# ModemExt2.net
KiCad netlist of a schematic drawn in Altium Designer
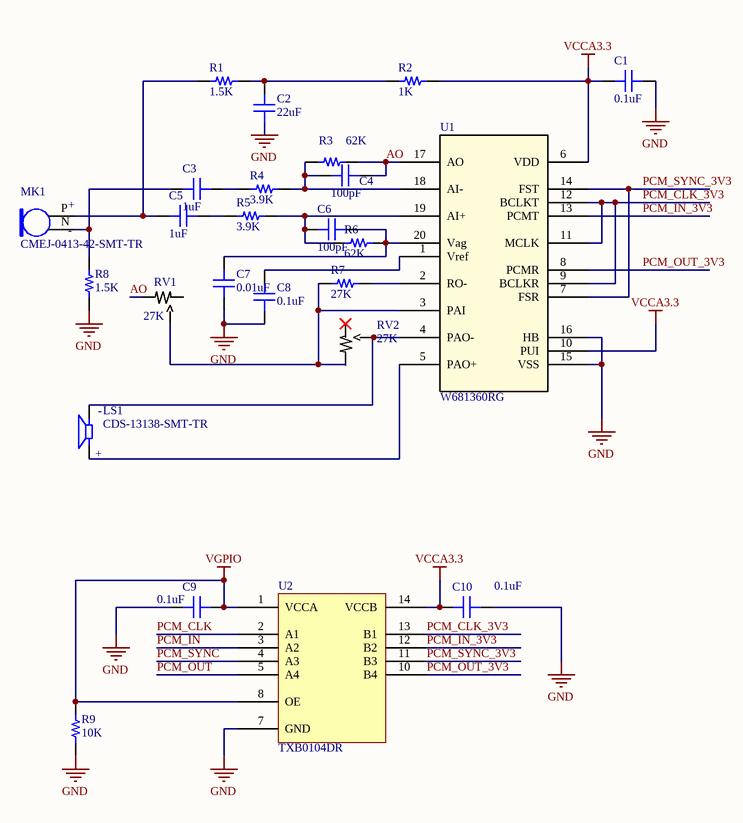
[diagram p0: ModemExt2.SchDoc]

(export (version "E")
  (design (tool "Eeschema 10.0.6"))
  (components
    (comp (ref "C1")
      (value "0.1uF")
      (footprint "CAP 0402_1005")
      (description "CAP CER 2.2UF 10V X5R 0402\r\ngrm155r61a")
      (fields
        (field (name "PART NUMBER") "GRM155R61A225ME95D")
        (field (name "MANUFACTURER") "Murata Electronics")
      )
      (libsource (lib "Celestial Altium Library - altium_library") (part "Capacitor"))
    )
    (comp (ref "C2")
      (value "22uF")
      (footprint "CAP 0402_1005")
      (description "CAP CER 2.2UF 10V X5R 0402\r\ngrm155r61a")
      (fields
        (field (name "PART NUMBER") "GRM155R61A225ME95D")
        (field (name "MANUFACTURER") "Murata Electronics")
      )
      (libsource (lib "Celestial Altium Library - altium_library") (part "Capacitor"))
    )
    (comp (ref "C3")
      (value "1uF")
      (footprint "CAP 0402_1005")
      (description "CAP CER 2.2UF 10V X5R 0402\r\ngrm155r61a")
      (fields
        (field (name "PART NUMBER") "GRM155R61A225ME95D")
        (field (name "MANUFACTURER") "Murata Electronics")
      )
      (libsource (lib "Celestial Altium Library - altium_library") (part "Capacitor"))
    )
    (comp (ref "C4")
      (value "100pF")
      (footprint "CAP 0402_1005")
      (description "CAP CER 2.2UF 10V X5R 0402\r\ngrm155r61a")
      (fields
        (field (name "PART NUMBER") "GRM155R61A225ME95D")
        (field (name "MANUFACTURER") "Murata Electronics")
      )
      (libsource (lib "Celestial Altium Library - altium_library") (part "Capacitor"))
    )
    (comp (ref "C5")
      (value "1uF")
      (footprint "CAP 0402_1005")
      (description "CAP CER 2.2UF 10V X5R 0402\r\ngrm155r61a")
      (fields
        (field (name "PART NUMBER") "GRM155R61A225ME95D")
        (field (name "MANUFACTURER") "Murata Electronics")
      )
      (libsource (lib "Celestial Altium Library - altium_library") (part "Capacitor"))
    )
    (comp (ref "C6")
      (value "100pF")
      (footprint "CAP 0402_1005")
      (description "CAP CER 2.2UF 10V X5R 0402\r\ngrm155r61a")
      (fields
        (field (name "PART NUMBER") "GRM155R61A225ME95D")
        (field (name "MANUFACTURER") "Murata Electronics")
      )
      (libsource (lib "Celestial Altium Library - altium_library") (part "Capacitor"))
    )
    (comp (ref "C7")
      (value "0.01uF")
      (footprint "CAP 0402_1005")
      (description "CAP CER 2.2UF 10V X5R 0402\r\ngrm155r61a")
      (fields
        (field (name "PART NUMBER") "GRM155R61A225ME95D")
        (field (name "MANUFACTURER") "Murata Electronics")
      )
      (libsource (lib "Celestial Altium Library - altium_library") (part "Capacitor"))
    )
    (comp (ref "C8")
      (value "0.1uF")
      (footprint "CAP 0402_1005")
      (description "CAP CER 2.2UF 10V X5R 0402\r\ngrm155r61a")
      (fields
        (field (name "PART NUMBER") "GRM155R61A225ME95D")
        (field (name "MANUFACTURER") "Murata Electronics")
      )
      (libsource (lib "Celestial Altium Library - altium_library") (part "Capacitor"))
    )
    (comp (ref "C9")
      (value "0.1uF")
      (footprint "CAP 0402_1005")
      (description "CAP CER 2.2UF 10V X5R 0402\r\ngrm155r61a")
      (fields
        (field (name "PART NUMBER") "GRM155R61A225ME95D")
        (field (name "MANUFACTURER") "Murata Electronics")
      )
      (libsource (lib "Celestial Altium Library - altium_library") (part "Capacitor"))
    )
    (comp (ref "C10")
      (value "0.1uF")
      (footprint "CAP 0402_1005")
      (description "CAP CER 2.2UF 10V X5R 0402\r\ngrm155r61a")
      (fields
        (field (name "PART NUMBER") "GRM155R61A225ME95D")
        (field (name "MANUFACTURER") "Murata Electronics")
      )
      (libsource (lib "Celestial Altium Library - altium_library") (part "Capacitor"))
    )
    (comp (ref "LS1")
      (value "CDS-13138-SMT-TR")
      (footprint "SPKR_CDS-13138-SMT-TR")
      (description "13 mm, Square Frame, 0.7 W, 8 Ohm, Samarium Cobalt Magnet, Mylar Cone")
      (fields (field (name "MF") "CUI Devices"))
      (libsource (lib "Schlib1") (part "CDS-13138-SMT-TR"))
    )
    (comp (ref "MK1")
      (value "CMEJ-0413-42-SMT-TR")
      (footprint "MIC_CMEJ-0413-42-SMT-TR")
      (description "4.0 mm, Omnidirectional, Surface Mount, 2 Vdc, Electret Condenser Microphone")
      (fields (field (name "MF") "CUI Devices"))
      (libsource (lib "Schlib1") (part "CMEJ-0413-42-SMT-TR"))
    )
    (comp (ref "R1")
      (value "1.5K")
      (footprint "RES 0603_1608")
      (description "RES SMD 10K OHM 1% 1/10W 0603")
      (fields (field (name "PART NUMBER") "AC0603FR-0710KL") (field (name "MANUFACTURER") "Yageo"))
      (libsource (lib "Celestial Altium Library - altium_library") (part "Resistor"))
    )
    (comp (ref "R2")
      (value "1K")
      (footprint "RES 0603_1608")
      (description "RES SMD 10K OHM 1% 1/10W 0603")
      (fields (field (name "PART NUMBER") "AC0603FR-0710KL") (field (name "MANUFACTURER") "Yageo"))
      (libsource (lib "Celestial Altium Library - altium_library") (part "Resistor"))
    )
    (comp (ref "R3")
      (value "62K")
      (footprint "RES 0603_1608")
      (description "RES SMD 10K OHM 1% 1/10W 0603")
      (fields (field (name "PART NUMBER") "AC0603FR-0710KL") (field (name "MANUFACTURER") "Yageo"))
      (libsource (lib "Celestial Altium Library - altium_library") (part "Resistor"))
    )
    (comp (ref "R4")
      (value "3.9K")
      (footprint "RES 0603_1608")
      (description "RES SMD 10K OHM 1% 1/10W 0603")
      (fields (field (name "PART NUMBER") "AC0603FR-0710KL") (field (name "MANUFACTURER") "Yageo"))
      (libsource (lib "Celestial Altium Library - altium_library") (part "Resistor"))
    )
    (comp (ref "R5")
      (value "3.9K")
      (footprint "RES 0603_1608")
      (description "RES SMD 10K OHM 1% 1/10W 0603")
      (fields (field (name "PART NUMBER") "AC0603FR-0710KL") (field (name "MANUFACTURER") "Yageo"))
      (libsource (lib "Celestial Altium Library - altium_library") (part "Resistor"))
    )
    (comp (ref "R6")
      (value "62K")
      (footprint "RES 0603_1608")
      (description "RES SMD 10K OHM 1% 1/10W 0603")
      (fields (field (name "PART NUMBER") "AC0603FR-0710KL") (field (name "MANUFACTURER") "Yageo"))
      (libsource (lib "Celestial Altium Library - altium_library") (part "Resistor"))
    )
    (comp (ref "R7")
      (value "27K")
      (footprint "RES 0603_1608")
      (description "RES SMD 10K OHM 1% 1/10W 0603")
      (fields (field (name "PART NUMBER") "AC0603FR-0710KL") (field (name "MANUFACTURER") "Yageo"))
      (libsource (lib "Celestial Altium Library - altium_library") (part "Resistor"))
    )
    (comp (ref "R8")
      (value "1.5K")
      (footprint "RES 0603_1608")
      (description "RES SMD 10K OHM 1% 1/10W 0603")
      (fields (field (name "PART NUMBER") "AC0603FR-0710KL") (field (name "MANUFACTURER") "Yageo"))
      (libsource (lib "Celestial Altium Library - altium_library") (part "Resistor"))
    )
    (comp (ref "R9")
      (value "10K")
      (footprint "RES 0603_1608")
      (description "RES SMD 10K OHM 1% 1/10W 0603")
      (fields (field (name "PART NUMBER") "AC0603FR-0710KL") (field (name "MANUFACTURER") "Yageo"))
      (libsource (lib "Celestial Altium Library - altium_library") (part "Resistor"))
    )
    (comp (ref "RV1")
      (value "27K")
      (footprint "*TRIM_3313J-1-503E")
      (fields (field (name "Comment") "3313J-1-503E"))
      (libsource (lib "Schlib1") (part "3313J-1-503E"))
    )
    (comp (ref "RV2")
      (value "27K")
      (footprint "*TRIM_3313J-1-503E")
      (fields (field (name "Comment") "3313J-1-503E"))
      (libsource (lib "Schlib1") (part "3313J-1-503E"))
    )
    (comp (ref "U1")
      (value "W681360RG")
      (footprint "SSOP20_MC_MCH")
      (description "No Description Available")
      (fields
        (field (name "MANUFACTURER_PART_NUMBER") "PIC16F685-E/SS")
        (field (name "COPYRIGHT") "Copyright (C) 2018 Accelerated Designs. All rights reserved")
      )
      (libsource (lib "Schlib1") (part "Audio Codec"))
    )
    (comp (ref "U2")
      (value "TXB0104DR")
      (footprint "TI SOIC-14 D")
      (description "IC TRNSLTR BIDIRECTIONAL 14SOIC")
      (fields (field (name "MANUFACTURER") "Texas Instruments"))
      (libsource (lib "Celestial Altium Library - altium_library") (part "TI TXB0104"))
    )
  )
  (nets
    (net (code "1") (name "/AO") (class "Default")
      (node (ref "C4") (pin "1") (pinfunction "1_1") (pintype "passive"))
      (node (ref "R3") (pin "1") (pinfunction "1_1") (pintype "passive"))
      (node (ref "RV1") (pin "1") (pinfunction "CCW_1") (pintype "passive"))
      (node (ref "U1") (pin "17") (pinfunction "AO_17") (pintype "passive"))
    )
    (net (code "2") (name "/PCM_CLK") (class "Default")
      (node (ref "U2") (pin "2") (pinfunction "A1_2") (pintype "passive"))
    )
    (net (code "3") (name "/PCM_CLK_3V3") (class "Default")
      (node (ref "U1") (pin "11") (pinfunction "MCLK_11") (pintype "passive"))
      (node (ref "U1") (pin "12") (pinfunction "BCLKT_12") (pintype "passive"))
      (node (ref "U1") (pin "9") (pinfunction "BCLKR_9") (pintype "passive"))
      (node (ref "U2") (pin "13") (pinfunction "B1_13") (pintype "passive"))
    )
    (net (code "4") (name "/PCM_IN") (class "Default")
      (node (ref "U2") (pin "3") (pinfunction "A2_3") (pintype "passive"))
    )
    (net (code "5") (name "/PCM_IN_3V3") (class "Default")
      (node (ref "U1") (pin "13") (pinfunction "PCMT_13") (pintype "passive"))
      (node (ref "U2") (pin "12") (pinfunction "B2_12") (pintype "passive"))
    )
    (net (code "6") (name "/PCM_OUT") (class "Default")
      (node (ref "U2") (pin "5") (pinfunction "A4_5") (pintype "passive"))
    )
    (net (code "7") (name "/PCM_OUT_3V3") (class "Default")
      (node (ref "U1") (pin "8") (pinfunction "PCMR_8") (pintype "passive"))
      (node (ref "U2") (pin "10") (pinfunction "B4_10") (pintype "passive"))
    )
    (net (code "8") (name "/PCM_SYNC") (class "Default")
      (node (ref "U2") (pin "4") (pinfunction "A3_4") (pintype "passive"))
    )
    (net (code "9") (name "/PCM_SYNC_3V3") (class "Default")
      (node (ref "U1") (pin "14") (pinfunction "FST_14") (pintype "passive"))
      (node (ref "U1") (pin "7") (pinfunction "FSR_7") (pintype "passive"))
      (node (ref "U2") (pin "11") (pinfunction "B3_11") (pintype "passive"))
    )
    (net (code "10") (name "GND") (class "Default")
      (node (ref "C1") (pin "1") (pinfunction "1_1") (pintype "passive"))
      (node (ref "C10") (pin "2") (pinfunction "2_2") (pintype "passive"))
      (node (ref "C2") (pin "2") (pinfunction "2_2") (pintype "passive"))
      (node (ref "C7") (pin "2") (pinfunction "2_2") (pintype "passive"))
      (node (ref "C8") (pin "2") (pinfunction "2_2") (pintype "passive"))
      (node (ref "C9") (pin "1") (pinfunction "1_1") (pintype "passive"))
      (node (ref "R8") (pin "2") (pinfunction "2_2") (pintype "passive"))
      (node (ref "R9") (pin "2") (pinfunction "2_2") (pintype "passive"))
      (node (ref "U1") (pin "15") (pinfunction "VSS_15") (pintype "passive"))
      (node (ref "U1") (pin "16") (pinfunction "HB_16") (pintype "passive"))
      (node (ref "U2") (pin "7") (pinfunction "GND_7") (pintype "passive"))
    )
    (net (code "11") (name "Net-(C2-Pad1)") (class "Default")
      (node (ref "C2") (pin "1") (pinfunction "1_1") (pintype "passive"))
      (node (ref "R1") (pin "1") (pinfunction "1_1") (pintype "passive"))
      (node (ref "R2") (pin "2") (pinfunction "2_2") (pintype "passive"))
    )
    (net (code "12") (name "Net-(C3-Pad1)") (class "Default")
      (node (ref "C3") (pin "1") (pinfunction "1_1") (pintype "passive"))
      (node (ref "R4") (pin "2") (pinfunction "2_2") (pintype "passive"))
    )
    (net (code "13") (name "Net-(C5-Pad1)") (class "Default")
      (node (ref "C5") (pin "1") (pinfunction "1_1") (pintype "passive"))
      (node (ref "R5") (pin "2") (pinfunction "2_2") (pintype "passive"))
    )
    (net (code "14") (name "Net-(MK1-GND)") (class "Default")
      (node (ref "C3") (pin "2") (pinfunction "2_2") (pintype "passive"))
      (node (ref "MK1") (pin "N") (pinfunction "GND_N") (pintype "passive"))
      (node (ref "R8") (pin "1") (pinfunction "1_1") (pintype "passive"))
    )
    (net (code "15") (name "Net-(MK1-OUTPUT)") (class "Default")
      (node (ref "C5") (pin "2") (pinfunction "2_2") (pintype "passive"))
      (node (ref "MK1") (pin "P") (pinfunction "OUTPUT_P") (pintype "passive"))
      (node (ref "R1") (pin "2") (pinfunction "2_2") (pintype "passive"))
    )
    (net (code "16") (name "Net-(RV1-WIPER)") (class "Default")
      (node (ref "R7") (pin "2") (pinfunction "2_2") (pintype "passive"))
      (node (ref "RV1") (pin "2") (pinfunction "WIPER_2") (pintype "passive"))
      (node (ref "RV2") (pin "1") (pinfunction "CCW_1") (pintype "passive"))
      (node (ref "U1") (pin "3") (pinfunction "PAI_3") (pintype "passive"))
    )
    (net (code "17") (name "Net-(RV2-WIPER)") (class "Default")
      (node (ref "LS1") (pin "M") (pinfunction "M_M") (pintype "passive"))
      (node (ref "RV2") (pin "2") (pinfunction "WIPER_2") (pintype "passive"))
      (node (ref "U1") (pin "4") (pinfunction "PAO-_4") (pintype "passive"))
    )
    (net (code "18") (name "Net-(U1-AI+)") (class "Default")
      (node (ref "C6") (pin "2") (pinfunction "2_2") (pintype "passive"))
      (node (ref "R5") (pin "1") (pinfunction "1_1") (pintype "passive"))
      (node (ref "R6") (pin "2") (pinfunction "2_2") (pintype "passive"))
      (node (ref "U1") (pin "19") (pinfunction "AI+_19") (pintype "passive"))
    )
    (net (code "19") (name "Net-(U1-AI-)") (class "Default")
      (node (ref "C4") (pin "2") (pinfunction "2_2") (pintype "passive"))
      (node (ref "R3") (pin "2") (pinfunction "2_2") (pintype "passive"))
      (node (ref "R4") (pin "1") (pinfunction "1_1") (pintype "passive"))
      (node (ref "U1") (pin "18") (pinfunction "AI-_18") (pintype "passive"))
    )
    (net (code "20") (name "Net-(U1-PAO+)") (class "Default")
      (node (ref "LS1") (pin "P") (pinfunction "P_P") (pintype "passive"))
      (node (ref "U1") (pin "5") (pinfunction "PAO+_5") (pintype "passive"))
    )
    (net (code "21") (name "Net-(U1-RO-)") (class "Default")
      (node (ref "R7") (pin "1") (pinfunction "1_1") (pintype "passive"))
      (node (ref "U1") (pin "2") (pinfunction "RO-_2") (pintype "passive"))
    )
    (net (code "22") (name "Net-(U1-Vag)") (class "Default")
      (node (ref "C6") (pin "1") (pinfunction "1_1") (pintype "passive"))
      (node (ref "C7") (pin "1") (pinfunction "1_1") (pintype "passive"))
      (node (ref "R6") (pin "1") (pinfunction "1_1") (pintype "passive"))
      (node (ref "U1") (pin "20") (pinfunction "Vag_20") (pintype "passive"))
    )
    (net (code "23") (name "Net-(U1-Vref)") (class "Default")
      (node (ref "C8") (pin "1") (pinfunction "1_1") (pintype "passive"))
      (node (ref "U1") (pin "1") (pinfunction "Vref_1") (pintype "passive"))
    )
    (net (code "24") (name "VCCA3.3") (class "Default")
      (node (ref "C1") (pin "2") (pinfunction "2_2") (pintype "passive"))
      (node (ref "C10") (pin "1") (pinfunction "1_1") (pintype "passive"))
      (node (ref "R2") (pin "1") (pinfunction "1_1") (pintype "passive"))
      (node (ref "U1") (pin "10") (pinfunction "PUI_10") (pintype "passive"))
      (node (ref "U1") (pin "6") (pinfunction "VDD_6") (pintype "passive"))
      (node (ref "U2") (pin "14") (pinfunction "VCCB_14") (pintype "passive"))
    )
    (net (code "25") (name "VGPIO") (class "Default")
      (node (ref "C9") (pin "2") (pinfunction "2_2") (pintype "passive"))
      (node (ref "R9") (pin "1") (pinfunction "1_1") (pintype "passive"))
      (node (ref "U2") (pin "1") (pinfunction "VCCA_1") (pintype "passive"))
      (node (ref "U2") (pin "8") (pinfunction "OE_8") (pintype "passive"))
    )
    (net (code "26") (name "unconnected-(RV1-CW-Pad3)") (class "Default")
      (node (ref "RV1") (pin "3") (pinfunction "CW_3") (pintype "passive"))
    )
    (net (code "27") (name "unconnected-(RV2-CW-Pad3)") (class "Default")
      (node (ref "RV2") (pin "3") (pinfunction "CW_3") (pintype "passive+no_connect"))
    )
  )
)
